# CAN.net
KiCad netlist of a schematic drawn in Altium Designer
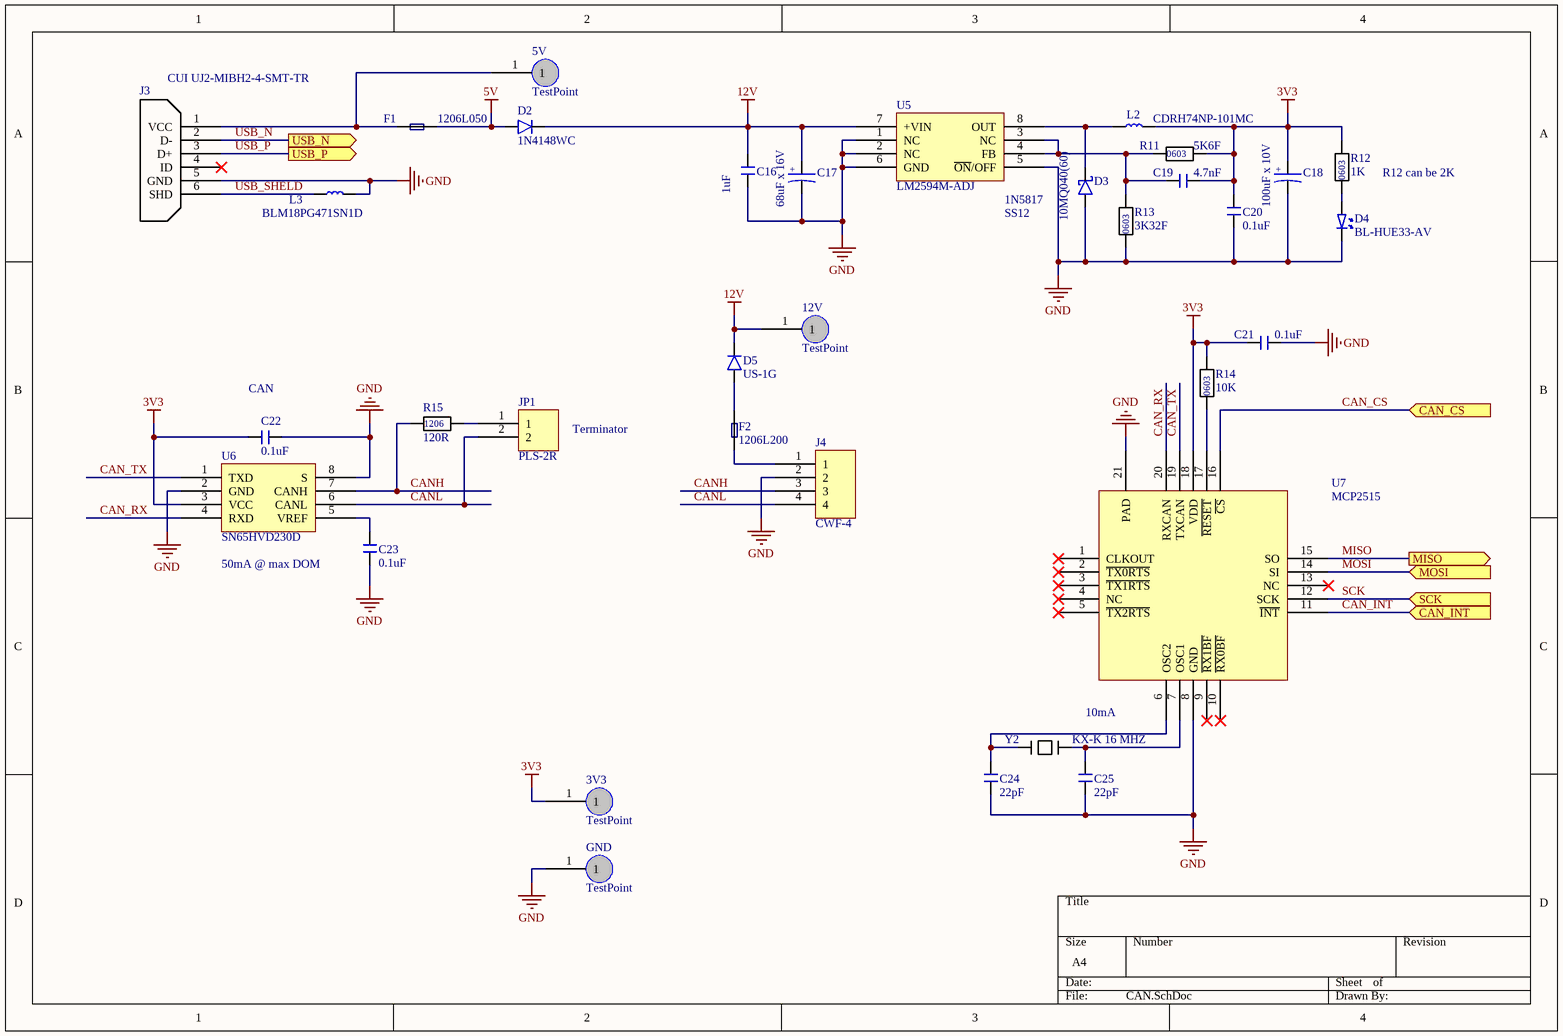
[diagram p0: CAN.SchDoc]

(export (version "E")
  (design (tool "Eeschema 10.0.6"))
  (components
    (comp (ref "3V3")
      (value "TestPoint")
      (footprint "TestPoint")
      (libsource (lib "Popular") (part "TestPoint"))
    )
    (comp (ref "5V")
      (value "TestPoint")
      (footprint "TestPoint")
      (libsource (lib "Popular") (part "TestPoint"))
    )
    (comp (ref "12V")
      (value "TestPoint")
      (footprint "TestPoint")
      (libsource (lib "Popular") (part "TestPoint"))
    )
    (comp (ref "C16") (value "1uF") (footprint "CHIP_C_0805") (libsource (lib "Popular") (part "CHIP_C")))
    (comp (ref "C17")
      (value "68uF x 16V")
      (footprint "TANTAL - C")
      (libsource (lib "Popular") (part "Tantal"))
    )
    (comp (ref "C18")
      (value "100uF x 10V")
      (footprint "Tantal - B")
      (libsource (lib "Popular") (part "Tantal"))
    )
    (comp (ref "C19") (value "4.7nF") (footprint "CHIP_C_0603") (libsource (lib "Popular") (part "CHIP_C")))
    (comp (ref "C20") (value "0.1uF") (footprint "CHIP_C_0603") (libsource (lib "Popular") (part "CHIP_C")))
    (comp (ref "C21") (value "0.1uF") (footprint "CHIP_C_0603") (libsource (lib "Popular") (part "CHIP_C")))
    (comp (ref "C22") (value "0.1uF") (footprint "CHIP_C_0603") (libsource (lib "Popular") (part "CHIP_C")))
    (comp (ref "C23") (value "0.1uF") (footprint "CHIP_C_0603") (libsource (lib "Popular") (part "CHIP_C")))
    (comp (ref "C24") (value "22pF") (footprint "CHIP_C_0603") (libsource (lib "Popular") (part "CHIP_C")))
    (comp (ref "C25") (value "22pF") (footprint "CHIP_C_0603") (libsource (lib "Popular") (part "CHIP_C")))
    (comp (ref "D2") (value "1N4148WC") (footprint "SOD323") (libsource (lib "Popular") (part "1N4148WC")))
    (comp (ref "D3")
      (value "10MQ040(60)")
      (footprint "DO214-AC")
      (description "Rectifier diode")
      (libsource (lib "Popular") (part "10MQ040"))
    )
    (comp (ref "D4")
      (value "BL-HUE33-AV")
      (footprint "CHIP_D_0603")
      (description "LED")
      (libsource (lib "Popular") (part "KP-3216"))
    )
    (comp (ref "D5") (value "US-1G") (footprint "DO214-AC") (libsource (lib "Popular") (part "US-1G")))
    (comp (ref "F1")
      (value "1206L050")
      (footprint "1206Lxxx")
      (description "Fuse")
      (libsource (lib "Popular") (part "miniSMDC014F-2"))
    )
    (comp (ref "F2")
      (value "1206L200")
      (footprint "1206Lxxx")
      (libsource (lib "Popular") (part "miniSMDC014F-2"))
    )
    (comp (ref "GND")
      (value "TestPoint")
      (footprint "TestPoint")
      (libsource (lib "Popular") (part "TestPoint"))
    )
    (comp (ref "J3")
      (value "CUI UJ2-MIBH2-4-SMT-TR")
      (footprint "MicroUSB-mc-258")
      (description "Micro USB connector")
      (libsource (lib "Popular") (part "USB_micro"))
    )
    (comp (ref "J4") (value "CWF-4") (footprint "CWF-4R") (libsource (lib "Popular") (part "CWF-4")))
    (comp (ref "JP1") (value "PLS-2R") (footprint "PLS-2R") (libsource (lib "Popular") (part "PLS-2")))
    (comp (ref "L2")
      (value "CDRH74NP-101MC")
      (footprint "CDRH74")
      (description "Ferrite drum core construction")
      (libsource (lib "Popular") (part "CDRH74"))
    )
    (comp (ref "L3")
      (value "BLM18PG471SN1D")
      (footprint "CHIP_R_0603")
      (libsource (lib "Popular") (part "BLM"))
    )
    (comp (ref "R11") (value "5K6F") (footprint "CHIP_R_0603") (libsource (lib "Popular") (part "RES_0603")))
    (comp (ref "R12") (value "1K") (footprint "CHIP_R_0603") (libsource (lib "Popular") (part "RES_0603")))
    (comp (ref "R13") (value "3K32F") (footprint "CHIP_R_0603") (libsource (lib "Popular") (part "RES_0603")))
    (comp (ref "R14") (value "10K") (footprint "CHIP_R_0603") (libsource (lib "Popular") (part "RES_0603")))
    (comp (ref "R15") (value "120R") (footprint "CHIP_R_1206") (libsource (lib "Popular") (part "RES_1206")))
    (comp (ref "U5") (value "LM2594M-ADJ") (footprint "SOIC8") (libsource (lib "Popular") (part "LM2594")))
    (comp (ref "U6") (value "SN65HVD230D") (footprint "SOIC8") (libsource (lib "Popular") (part "TJA1050")))
    (comp (ref "U7") (value "MCP2515") (footprint "QFN20") (libsource (lib "Popular") (part "MCP2515_QFN")))
    (comp (ref "Y2")
      (value "KX-K 16 MHZ")
      (footprint "CHIP_CRYSTAL_5032")
      (libsource (lib "Popular") (part "Quartz"))
    )
  )
  (nets
    (net (code "1") (name "/CANH") (class "Default")
      (node (ref "J4") (pin "3") (pinfunction "3_3") (pintype "passive"))
      (node (ref "R15") (pin "1") (pinfunction "1_1") (pintype "passive"))
      (node (ref "U6") (pin "7") (pinfunction "CANH_7") (pintype "passive"))
    )
    (net (code "2") (name "/CANL") (class "Default")
      (node (ref "J4") (pin "4") (pinfunction "4_4") (pintype "passive"))
      (node (ref "JP1") (pin "2") (pinfunction "2_2") (pintype "passive"))
      (node (ref "U6") (pin "6") (pinfunction "CANL_6") (pintype "passive"))
    )
    (net (code "3") (name "/CAN_CS") (class "Default")
      (node (ref "U7") (pin "16") (pinfunction "~{CS}_16") (pintype "passive"))
    )
    (net (code "4") (name "/CAN_INT") (class "Default")
      (node (ref "U7") (pin "11") (pinfunction "~{INT}_11") (pintype "passive"))
    )
    (net (code "5") (name "/CAN_RX") (class "Default")
      (node (ref "U6") (pin "4") (pinfunction "RXD_4") (pintype "passive"))
      (node (ref "U7") (pin "20") (pinfunction "RXCAN_20") (pintype "passive"))
    )
    (net (code "6") (name "/CAN_TX") (class "Default")
      (node (ref "U6") (pin "1") (pinfunction "TXD_1") (pintype "passive"))
      (node (ref "U7") (pin "19") (pinfunction "TXCAN_19") (pintype "passive"))
    )
    (net (code "7") (name "/MISO") (class "Default")
      (node (ref "U7") (pin "15") (pinfunction "SO_15") (pintype "passive"))
    )
    (net (code "8") (name "/MOSI") (class "Default")
      (node (ref "U7") (pin "14") (pinfunction "SI_14") (pintype "passive"))
    )
    (net (code "9") (name "/SCK") (class "Default")
      (node (ref "U7") (pin "12") (pinfunction "SCK_12") (pintype "passive"))
    )
    (net (code "10") (name "/USB_N") (class "Default")
      (node (ref "J3") (pin "2") (pinfunction "D-_2") (pintype "passive"))
    )
    (net (code "11") (name "/USB_P") (class "Default")
      (node (ref "J3") (pin "3") (pinfunction "D+_3") (pintype "passive"))
    )
    (net (code "12") (name "/USB_SHELD") (class "Default")
      (node (ref "J3") (pin "6") (pinfunction "SHD_6") (pintype "passive"))
      (node (ref "L3") (pin "1") (pinfunction "1_1") (pintype "passive"))
    )
    (net (code "13") (name "3V3") (class "Default")
      (node (ref "3V3") (pin "1") (pinfunction "1_1") (pintype "passive"))
      (node (ref "C18") (pin "1") (pinfunction "1_1") (pintype "passive"))
      (node (ref "C19") (pin "1") (pinfunction "1_1") (pintype "passive"))
      (node (ref "C20") (pin "2") (pinfunction "2_2") (pintype "passive"))
      (node (ref "C21") (pin "2") (pinfunction "2_2") (pintype "passive"))
      (node (ref "C22") (pin "2") (pinfunction "2_2") (pintype "passive"))
      (node (ref "L2") (pin "2") (pinfunction "2_2") (pintype "passive"))
      (node (ref "R11") (pin "2") (pinfunction "2_2") (pintype "passive"))
      (node (ref "R12") (pin "2") (pinfunction "2_2") (pintype "passive"))
      (node (ref "R14") (pin "2") (pinfunction "2_2") (pintype "passive"))
      (node (ref "U6") (pin "3") (pinfunction "VCC_3") (pintype "passive"))
      (node (ref "U7") (pin "18") (pinfunction "VDD_18") (pintype "passive"))
    )
    (net (code "14") (name "5V") (class "Default")
      (node (ref "D2") (pin "2") (pinfunction "2_2") (pintype "passive"))
      (node (ref "F1") (pin "2") (pinfunction "2_2") (pintype "passive"))
    )
    (net (code "15") (name "12V") (class "Default")
      (node (ref "12V") (pin "1") (pinfunction "1_1") (pintype "passive"))
      (node (ref "C16") (pin "2") (pinfunction "2_2") (pintype "passive"))
      (node (ref "C17") (pin "1") (pinfunction "1_1") (pintype "passive"))
      (node (ref "D2") (pin "1") (pinfunction "1_1") (pintype "passive"))
      (node (ref "D5") (pin "2") (pinfunction "2_2") (pintype "passive"))
      (node (ref "U5") (pin "7") (pinfunction "+VIN_7") (pintype "passive"))
    )
    (net (code "16") (name "GND") (class "Default")
      (node (ref "C16") (pin "1") (pinfunction "1_1") (pintype "passive"))
      (node (ref "C17") (pin "2") (pinfunction "2_2") (pintype "passive"))
      (node (ref "C18") (pin "2") (pinfunction "2_2") (pintype "passive"))
      (node (ref "C20") (pin "1") (pinfunction "1_1") (pintype "passive"))
      (node (ref "C21") (pin "1") (pinfunction "1_1") (pintype "passive"))
      (node (ref "C22") (pin "1") (pinfunction "1_1") (pintype "passive"))
      (node (ref "C23") (pin "1") (pinfunction "1_1") (pintype "passive"))
      (node (ref "C24") (pin "1") (pinfunction "1_1") (pintype "passive"))
      (node (ref "C25") (pin "1") (pinfunction "1_1") (pintype "passive"))
      (node (ref "D3") (pin "1") (pinfunction "1_1") (pintype "passive"))
      (node (ref "D4") (pin "2") (pinfunction "C_2") (pintype "passive"))
      (node (ref "GND") (pin "1") (pinfunction "1_1") (pintype "passive"))
      (node (ref "J3") (pin "5") (pinfunction "GND_5") (pintype "passive"))
      (node (ref "J4") (pin "2") (pinfunction "2_2") (pintype "passive"))
      (node (ref "L3") (pin "2") (pinfunction "2_2") (pintype "passive"))
      (node (ref "R13") (pin "1") (pinfunction "1_1") (pintype "passive"))
      (node (ref "U5") (pin "1") (pinfunction "NC_1") (pintype "passive"))
      (node (ref "U5") (pin "2") (pinfunction "NC_2") (pintype "passive"))
      (node (ref "U5") (pin "5") (pinfunction "~{ON}/OFF_5") (pintype "passive"))
      (node (ref "U5") (pin "6") (pinfunction "GND_6") (pintype "passive"))
      (node (ref "U6") (pin "2") (pinfunction "GND_2") (pintype "passive"))
      (node (ref "U6") (pin "8") (pinfunction "S_8") (pintype "passive"))
      (node (ref "U7") (pin "21") (pinfunction "PAD_21") (pintype "passive"))
      (node (ref "U7") (pin "8") (pinfunction "GND_8") (pintype "passive"))
    )
    (net (code "17") (name "Net-(D4-A)") (class "Default")
      (node (ref "D4") (pin "1") (pinfunction "A_1") (pintype "passive"))
      (node (ref "R12") (pin "1") (pinfunction "1_1") (pintype "passive"))
    )
    (net (code "18") (name "Net-(D5-Pad1)") (class "Default")
      (node (ref "D5") (pin "1") (pinfunction "1_1") (pintype "passive"))
      (node (ref "F2") (pin "2") (pinfunction "2_2") (pintype "passive"))
    )
    (net (code "19") (name "Net-(F2-Pad1)") (class "Default")
      (node (ref "F2") (pin "1") (pinfunction "1_1") (pintype "passive"))
      (node (ref "J4") (pin "1") (pinfunction "1_1") (pintype "passive"))
    )
    (net (code "20") (name "Net-(J3-VCC)") (class "Default")
      (node (ref "5V") (pin "1") (pinfunction "1_1") (pintype "passive"))
      (node (ref "F1") (pin "1") (pinfunction "1_1") (pintype "passive"))
      (node (ref "J3") (pin "1") (pinfunction "VCC_1") (pintype "passive"))
    )
    (net (code "21") (name "Net-(JP1-Pad1)") (class "Default")
      (node (ref "JP1") (pin "1") (pinfunction "1_1") (pintype "passive"))
      (node (ref "R15") (pin "2") (pinfunction "2_2") (pintype "passive"))
    )
    (net (code "22") (name "Net-(U5-FB)") (class "Default")
      (node (ref "C19") (pin "2") (pinfunction "2_2") (pintype "passive"))
      (node (ref "R11") (pin "1") (pinfunction "1_1") (pintype "passive"))
      (node (ref "R13") (pin "2") (pinfunction "2_2") (pintype "passive"))
      (node (ref "U5") (pin "3") (pinfunction "NC_3") (pintype "passive"))
      (node (ref "U5") (pin "4") (pinfunction "FB_4") (pintype "passive"))
    )
    (net (code "23") (name "Net-(U5-OUT)") (class "Default")
      (node (ref "D3") (pin "2") (pinfunction "2_2") (pintype "passive"))
      (node (ref "L2") (pin "1") (pinfunction "1_1") (pintype "passive"))
      (node (ref "U5") (pin "8") (pinfunction "OUT_8") (pintype "passive"))
    )
    (net (code "24") (name "Net-(U6-VREF)") (class "Default")
      (node (ref "C23") (pin "2") (pinfunction "2_2") (pintype "passive"))
      (node (ref "U6") (pin "5") (pinfunction "VREF_5") (pintype "passive"))
    )
    (net (code "25") (name "Net-(U7-OSC1)") (class "Default")
      (node (ref "C25") (pin "2") (pinfunction "2_2") (pintype "passive"))
      (node (ref "U7") (pin "7") (pinfunction "OSC1_7") (pintype "passive"))
      (node (ref "Y2") (pin "2") (pinfunction "2_2") (pintype "passive"))
    )
    (net (code "26") (name "Net-(U7-OSC2)") (class "Default")
      (node (ref "C24") (pin "2") (pinfunction "2_2") (pintype "passive"))
      (node (ref "U7") (pin "6") (pinfunction "OSC2_6") (pintype "passive"))
      (node (ref "Y2") (pin "1") (pinfunction "1_1") (pintype "passive"))
    )
    (net (code "27") (name "Net-(U7-~{RESET})") (class "Default")
      (node (ref "R14") (pin "1") (pinfunction "1_1") (pintype "passive"))
      (node (ref "U7") (pin "17") (pinfunction "~{RESET}_17") (pintype "passive"))
    )
    (net (code "28") (name "unconnected-(J3-ID-Pad4)") (class "Default")
      (node (ref "J3") (pin "4") (pinfunction "ID_4") (pintype "passive+no_connect"))
    )
    (net (code "29") (name "unconnected-(U7-CLKOUT-Pad1)") (class "Default")
      (node (ref "U7") (pin "1") (pinfunction "CLKOUT_1") (pintype "passive+no_connect"))
    )
    (net (code "30") (name "unconnected-(U7-NC-Pad4)") (class "Default")
      (node (ref "U7") (pin "4") (pinfunction "NC_4") (pintype "passive+no_connect"))
    )
    (net (code "31") (name "unconnected-(U7-NC-Pad13)") (class "Default")
      (node (ref "U7") (pin "13") (pinfunction "NC_13") (pintype "passive+no_connect"))
    )
    (net (code "32") (name "unconnected-(U7-~{RX0BF}-Pad10)") (class "Default")
      (node (ref "U7") (pin "10") (pinfunction "~{RX0BF}_10") (pintype "passive+no_connect"))
    )
    (net (code "33") (name "unconnected-(U7-~{RX1BF}-Pad9)") (class "Default")
      (node (ref "U7") (pin "9") (pinfunction "~{RX1BF}_9") (pintype "passive+no_connect"))
    )
    (net (code "34") (name "unconnected-(U7-~{TX0RTS}-Pad2)") (class "Default")
      (node (ref "U7") (pin "2") (pinfunction "~{TX0RTS}_2") (pintype "passive+no_connect"))
    )
    (net (code "35") (name "unconnected-(U7-~{TX1RTS}-Pad3)") (class "Default")
      (node (ref "U7") (pin "3") (pinfunction "~{TX1RTS}_3") (pintype "passive+no_connect"))
    )
    (net (code "36") (name "unconnected-(U7-~{TX2RTS}-Pad5)") (class "Default")
      (node (ref "U7") (pin "5") (pinfunction "~{TX2RTS}_5") (pintype "passive+no_connect"))
    )
  )
)
